# Top_Level.net
KiCad netlist of a schematic drawn in Altium Designer
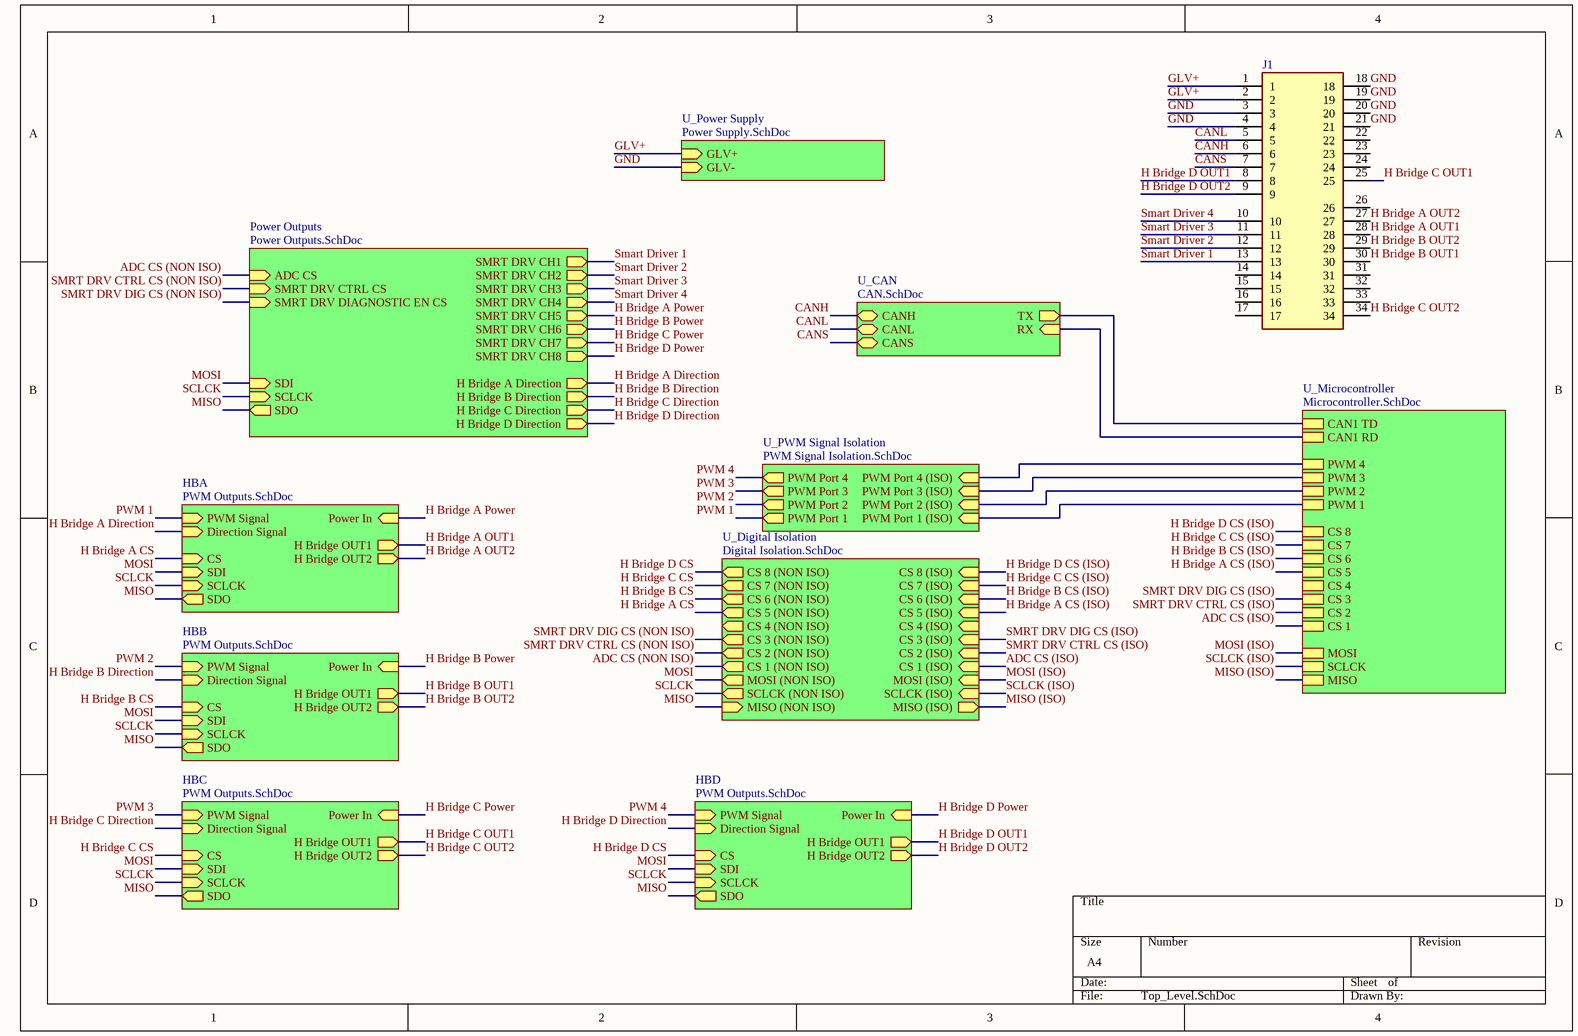
[diagram p0: Top_Level.SchDoc]

(export (version "E")
  (design (tool "Eeschema 10.0.6"))
  (components
    (comp (ref "J1")
      (value "~")
      (footprint "6437288-1")
      (description "34 Position 4 Row Right Angle Receptacle Through Hole Super Seal Cap Assy")
      (fields
        (field (name "MP") "6437288-1")
        (field (name "MF") "TE Connectivity")
        (field (name "CONTACT") "Gold")
      )
      (libsource (lib "ts_standard_connectors") (part "6437288-1"))
    )
  )
  (nets
    (net (code "4") (name "/CANH") (class "Default")
      (node (ref "J1") (pin "6") (pinfunction "6_6") (pintype "passive"))
    )
    (net (code "5") (name "/CANL") (class "Default")
      (node (ref "J1") (pin "5") (pinfunction "5_5") (pintype "passive"))
    )
    (net (code "6") (name "/CANS") (class "Default")
      (node (ref "J1") (pin "7") (pinfunction "7_7") (pintype "passive"))
    )
    (net (code "10") (name "/GLV+") (class "Default")
      (node (ref "J1") (pin "1") (pinfunction "1_1") (pintype "passive"))
      (node (ref "J1") (pin "2") (pinfunction "2_2") (pintype "passive"))
    )
    (net (code "11") (name "/GND") (class "Default")
      (node (ref "J1") (pin "18") (pinfunction "18_18") (pintype "passive"))
      (node (ref "J1") (pin "19") (pinfunction "19_19") (pintype "passive"))
      (node (ref "J1") (pin "20") (pinfunction "20_20") (pintype "passive"))
      (node (ref "J1") (pin "21") (pinfunction "21_21") (pintype "passive"))
      (node (ref "J1") (pin "3") (pinfunction "3_3") (pintype "passive"))
      (node (ref "J1") (pin "4") (pinfunction "4_4") (pintype "passive"))
    )
    (net (code "15") (name "/H Bridge A OUT1") (class "Default")
      (node (ref "J1") (pin "28") (pinfunction "28_28") (pintype "passive"))
    )
    (net (code "16") (name "/H Bridge A OUT2") (class "Default")
      (node (ref "J1") (pin "27") (pinfunction "27_27") (pintype "passive"))
    )
    (net (code "21") (name "/H Bridge B OUT1") (class "Default")
      (node (ref "J1") (pin "30") (pinfunction "30_30") (pintype "passive"))
    )
    (net (code "22") (name "/H Bridge B OUT2") (class "Default")
      (node (ref "J1") (pin "29") (pinfunction "29_29") (pintype "passive"))
    )
    (net (code "27") (name "/H Bridge C OUT1") (class "Default")
      (node (ref "J1") (pin "25") (pinfunction "25_25") (pintype "passive"))
    )
    (net (code "28") (name "/H Bridge C OUT2") (class "Default")
      (node (ref "J1") (pin "34") (pinfunction "34_34") (pintype "passive"))
    )
    (net (code "33") (name "/H Bridge D OUT1") (class "Default")
      (node (ref "J1") (pin "8") (pinfunction "8_8") (pintype "passive"))
    )
    (net (code "34") (name "/H Bridge D OUT2") (class "Default")
      (node (ref "J1") (pin "9") (pinfunction "9_9") (pintype "passive"))
    )
    (net (code "54") (name "/Smart Driver 1") (class "Default")
      (node (ref "J1") (pin "13") (pinfunction "13_13") (pintype "passive"))
    )
    (net (code "55") (name "/Smart Driver 2") (class "Default")
      (node (ref "J1") (pin "12") (pinfunction "12_12") (pintype "passive"))
    )
    (net (code "56") (name "/Smart Driver 3") (class "Default")
      (node (ref "J1") (pin "11") (pinfunction "11_11") (pintype "passive"))
    )
    (net (code "57") (name "/Smart Driver 4") (class "Default")
      (node (ref "J1") (pin "10") (pinfunction "10_10") (pintype "passive"))
    )
    (net (code "59") (name "unconnected-(J1-Pad14)") (class "Default")
      (node (ref "J1") (pin "14") (pinfunction "14_14") (pintype "passive"))
    )
    (net (code "60") (name "unconnected-(J1-Pad15)") (class "Default")
      (node (ref "J1") (pin "15") (pinfunction "15_15") (pintype "passive"))
    )
    (net (code "61") (name "unconnected-(J1-Pad16)") (class "Default")
      (node (ref "J1") (pin "16") (pinfunction "16_16") (pintype "passive"))
    )
    (net (code "62") (name "unconnected-(J1-Pad17)") (class "Default")
      (node (ref "J1") (pin "17") (pinfunction "17_17") (pintype "passive"))
    )
    (net (code "63") (name "unconnected-(J1-Pad22)") (class "Default")
      (node (ref "J1") (pin "22") (pinfunction "22_22") (pintype "passive"))
    )
    (net (code "64") (name "unconnected-(J1-Pad23)") (class "Default")
      (node (ref "J1") (pin "23") (pinfunction "23_23") (pintype "passive"))
    )
    (net (code "65") (name "unconnected-(J1-Pad24)") (class "Default")
      (node (ref "J1") (pin "24") (pinfunction "24_24") (pintype "passive"))
    )
    (net (code "66") (name "unconnected-(J1-Pad26)") (class "Default")
      (node (ref "J1") (pin "26") (pinfunction "26_26") (pintype "passive"))
    )
    (net (code "67") (name "unconnected-(J1-Pad31)") (class "Default")
      (node (ref "J1") (pin "31") (pinfunction "31_31") (pintype "passive"))
    )
    (net (code "68") (name "unconnected-(J1-Pad32)") (class "Default")
      (node (ref "J1") (pin "32") (pinfunction "32_32") (pintype "passive"))
    )
    (net (code "69") (name "unconnected-(J1-Pad33)") (class "Default")
      (node (ref "J1") (pin "33") (pinfunction "33_33") (pintype "passive"))
    )
  )
)
